# BuzzerBaseShieldv11.net
KiCad netlist of a schematic drawn in EAGLE
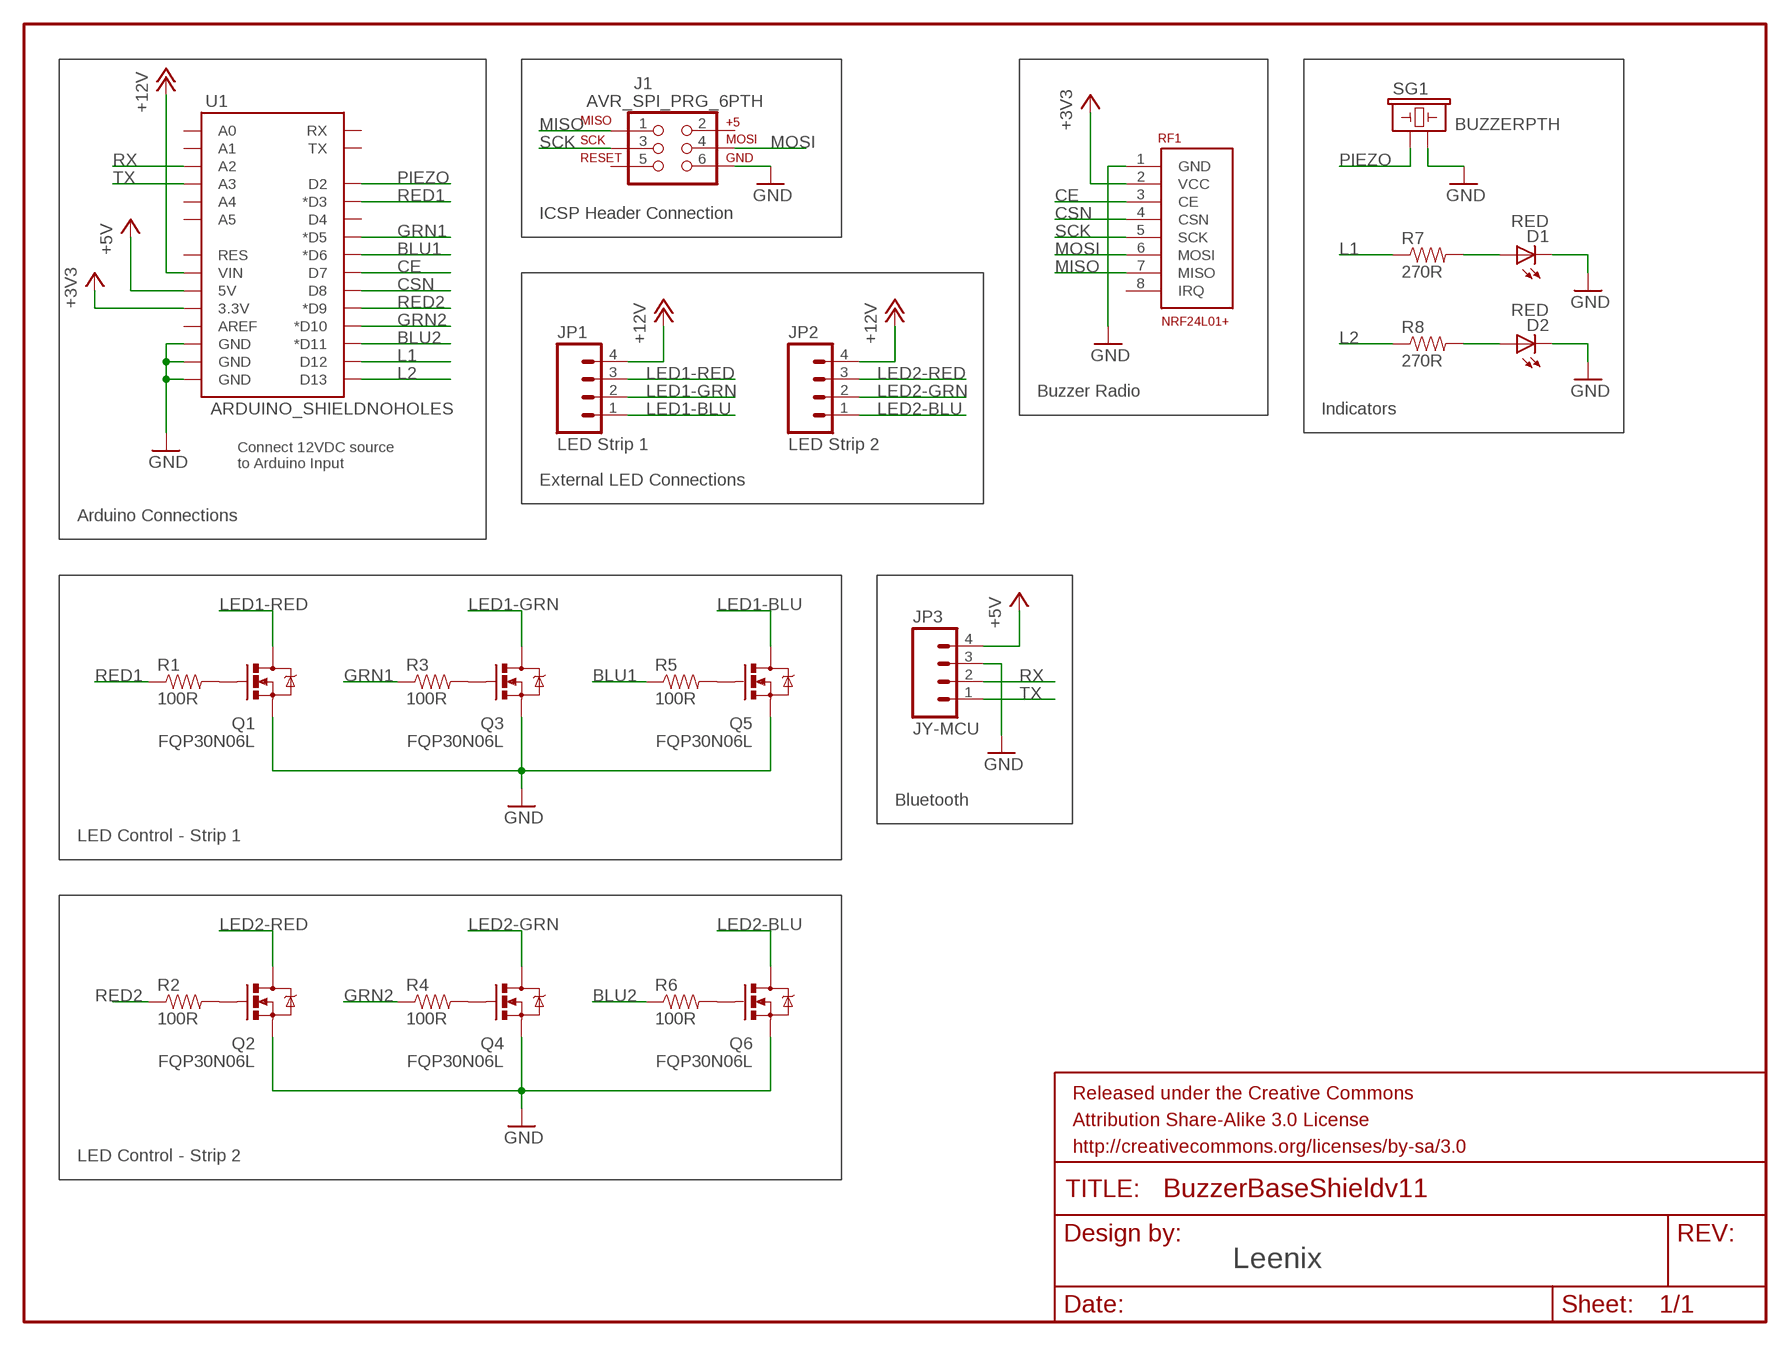
[diagram p0: schematic, sheet 1, part 1 of 2]
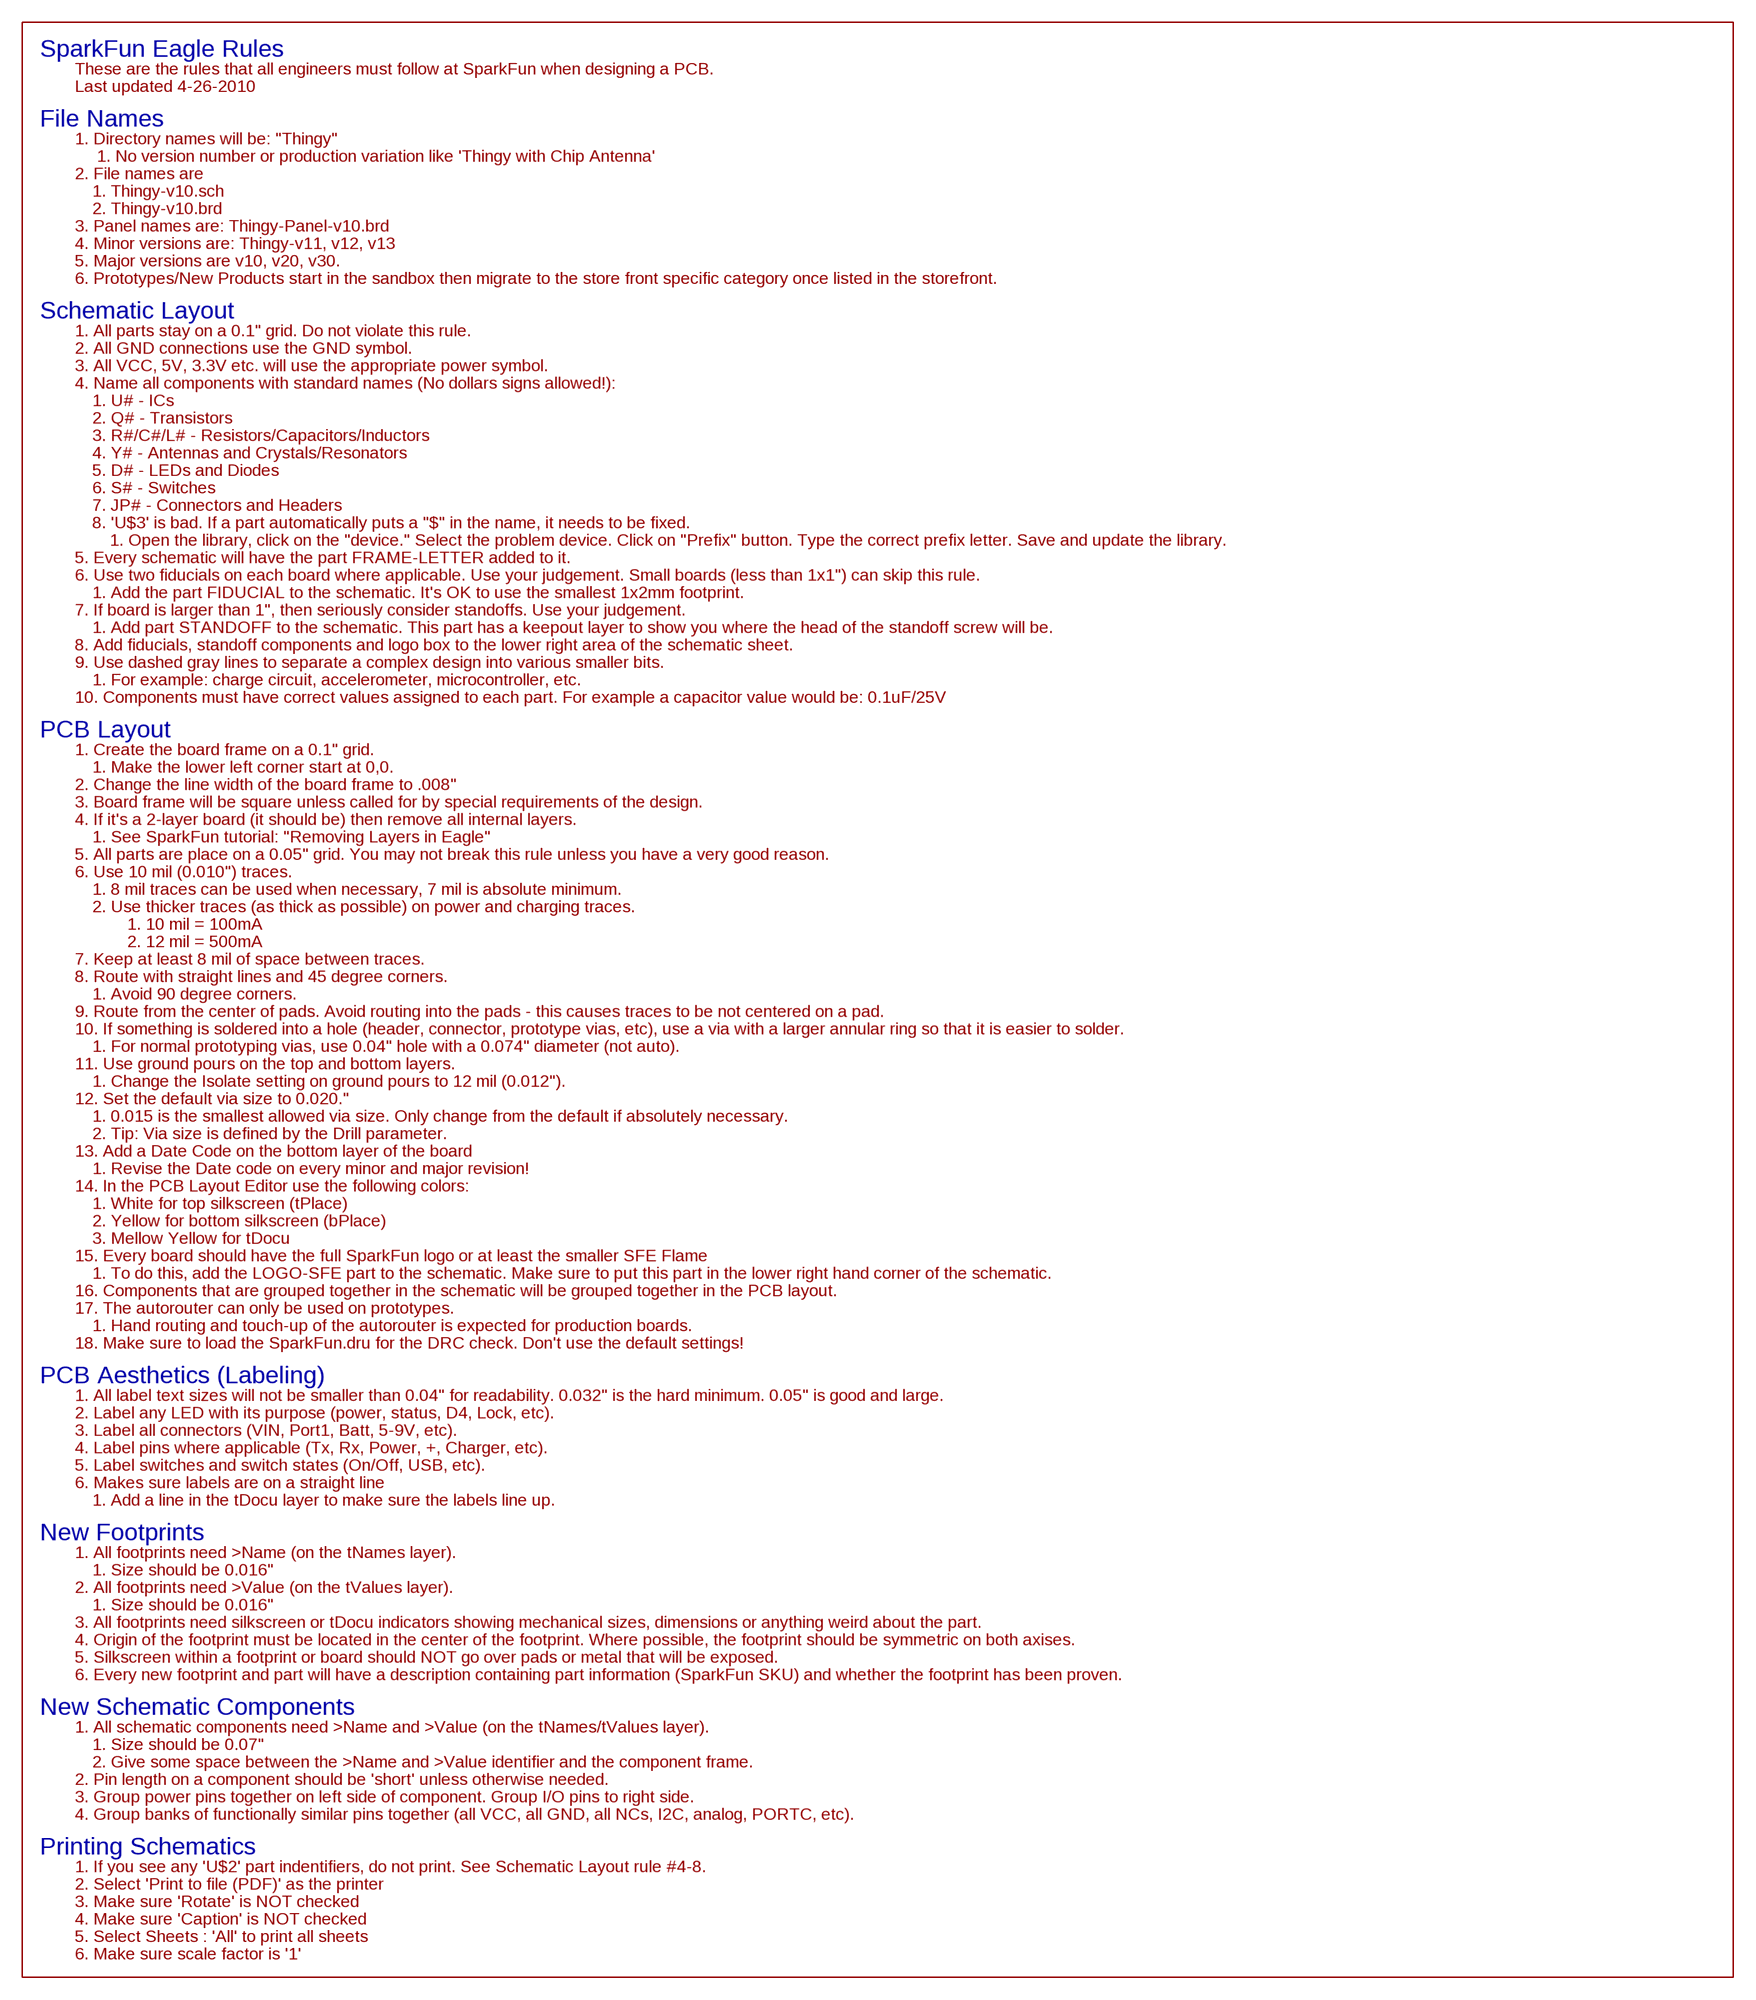
[diagram p1: schematic, sheet 1, part 2 of 2]

(export (version "E")
  (design (tool "Eeschema 10.0.6"))
  (components
    (comp (ref "D1")
      (value "RED")
      (footprint "eagle-import:LED-1206")
      (libsource (lib "eagle-import") (part "LED-RED1206"))
    )
    (comp (ref "D2")
      (value "RED")
      (footprint "eagle-import:LED-1206")
      (libsource (lib "eagle-import") (part "LED-RED1206"))
    )
    (comp (ref "FRAME1")
      (value "FRAME-LETTER")
      (footprint "eagle-import:CREATIVE_COMMONS")
      (libsource (lib "eagle-import") (part "FRAME-LETTER"))
    )
    (comp (ref "J1")
      (value "AVR_SPI_PRG_6PTH")
      (footprint "eagle-import:2X3")
      (libsource (lib "eagle-import") (part "AVR_SPI_PRG_6PTH"))
    )
    (comp (ref "JP1")
      (value "LED Strip 1")
      (footprint "eagle-import:1X04_LONGPADS")
      (libsource (lib "eagle-import") (part "M04LONGPADS"))
    )
    (comp (ref "JP2")
      (value "LED Strip 2")
      (footprint "eagle-import:1X04_LONGPADS")
      (libsource (lib "eagle-import") (part "M04LONGPADS"))
    )
    (comp (ref "JP3")
      (value "JY-MCU")
      (footprint "eagle-import:1X04")
      (libsource (lib "eagle-import") (part "M04PTH"))
    )
    (comp (ref "Q1")
      (value "FQP30N06L")
      (footprint "eagle-import:TO220V")
      (libsource (lib "eagle-import") (part "MOSFET-NCHANNELFQP30N06L"))
    )
    (comp (ref "Q2")
      (value "FQP30N06L")
      (footprint "eagle-import:TO220V")
      (libsource (lib "eagle-import") (part "MOSFET-NCHANNELFQP30N06L"))
    )
    (comp (ref "Q3")
      (value "FQP30N06L")
      (footprint "eagle-import:TO220V")
      (libsource (lib "eagle-import") (part "MOSFET-NCHANNELFQP30N06L"))
    )
    (comp (ref "Q4")
      (value "FQP30N06L")
      (footprint "eagle-import:TO220V")
      (libsource (lib "eagle-import") (part "MOSFET-NCHANNELFQP30N06L"))
    )
    (comp (ref "Q5")
      (value "FQP30N06L")
      (footprint "eagle-import:TO220V")
      (libsource (lib "eagle-import") (part "MOSFET-NCHANNELFQP30N06L"))
    )
    (comp (ref "Q6")
      (value "FQP30N06L")
      (footprint "eagle-import:TO220V")
      (libsource (lib "eagle-import") (part "MOSFET-NCHANNELFQP30N06L"))
    )
    (comp (ref "R1")
      (value "100R")
      (footprint "eagle-import:1206")
      (libsource (lib "eagle-import") (part "RESISTOR1206"))
    )
    (comp (ref "R2")
      (value "100R")
      (footprint "eagle-import:1206")
      (libsource (lib "eagle-import") (part "RESISTOR1206"))
    )
    (comp (ref "R3")
      (value "100R")
      (footprint "eagle-import:1206")
      (libsource (lib "eagle-import") (part "RESISTOR1206"))
    )
    (comp (ref "R4")
      (value "100R")
      (footprint "eagle-import:1206")
      (libsource (lib "eagle-import") (part "RESISTOR1206"))
    )
    (comp (ref "R5")
      (value "100R")
      (footprint "eagle-import:1206")
      (libsource (lib "eagle-import") (part "RESISTOR1206"))
    )
    (comp (ref "R6")
      (value "100R")
      (footprint "eagle-import:1206")
      (libsource (lib "eagle-import") (part "RESISTOR1206"))
    )
    (comp (ref "R7")
      (value "270R")
      (footprint "eagle-import:1206")
      (libsource (lib "eagle-import") (part "RESISTOR1206"))
    )
    (comp (ref "R8")
      (value "270R")
      (footprint "eagle-import:1206")
      (libsource (lib "eagle-import") (part "RESISTOR1206"))
    )
    (comp (ref "RF1")
      (value "NRF24L01+")
      (footprint "eagle-import:NRF24L01+-HEADER")
      (libsource (lib "eagle-import") (part "NRF24L01+"))
    )
    (comp (ref "SG1")
      (value "BUZZERPTH")
      (footprint "eagle-import:BUZZER-12MM")
      (libsource (lib "eagle-import") (part "BUZZERPTH"))
    )
    (comp (ref "U1")
      (value "ARDUINO_SHIELDNOHOLES")
      (footprint "eagle-import:DUEMILANOVE_SHIELD_NOHOLES")
      (libsource (lib "eagle-import") (part "ARDUINO_SHIELDNOHOLES"))
    )
  )
  (nets
    (net (code "1") (name "+3V3") (class "Default")
      (node (ref "RF1") (pin "2") (pinfunction "VCC_2") (pintype "power_in"))
      (node (ref "U1") (pin "3.3V") (pinfunction "3.3V_3.3V") (pintype "bidirectional"))
    )
    (net (code "2") (name "+5V") (class "Default")
      (node (ref "JP3") (pin "4") (pinfunction "4_4") (pintype "passive"))
      (node (ref "U1") (pin "5V") (pinfunction "5V_5V") (pintype "bidirectional"))
    )
    (net (code "3") (name "+12V") (class "Default")
      (node (ref "JP1") (pin "4") (pinfunction "4_4") (pintype "passive"))
      (node (ref "JP2") (pin "4") (pinfunction "4_4") (pintype "passive"))
      (node (ref "U1") (pin "VIN") (pinfunction "VIN_VIN") (pintype "bidirectional"))
    )
    (net (code "4") (name "/BLU1") (class "Default")
      (node (ref "R5") (pin "1") (pinfunction "1_1") (pintype "passive"))
      (node (ref "U1") (pin "D6") (pinfunction "*D6_D6") (pintype "bidirectional"))
    )
    (net (code "5") (name "/BLU2") (class "Default")
      (node (ref "R6") (pin "1") (pinfunction "1_1") (pintype "passive"))
      (node (ref "U1") (pin "D11") (pinfunction "*D11_D11") (pintype "bidirectional"))
    )
    (net (code "6") (name "/CE") (class "Default")
      (node (ref "RF1") (pin "3") (pinfunction "CE_3") (pintype "bidirectional"))
      (node (ref "U1") (pin "D7") (pinfunction "D7_D7") (pintype "bidirectional"))
    )
    (net (code "7") (name "/CSN") (class "Default")
      (node (ref "RF1") (pin "4") (pinfunction "CSN_4") (pintype "bidirectional"))
      (node (ref "U1") (pin "D8") (pinfunction "D8_D8") (pintype "bidirectional"))
    )
    (net (code "8") (name "/GRN1") (class "Default")
      (node (ref "R3") (pin "1") (pinfunction "1_1") (pintype "passive"))
      (node (ref "U1") (pin "D5") (pinfunction "*D5_D5") (pintype "bidirectional"))
    )
    (net (code "9") (name "/GRN2") (class "Default")
      (node (ref "R4") (pin "1") (pinfunction "1_1") (pintype "passive"))
      (node (ref "U1") (pin "D10") (pinfunction "*D10_D10") (pintype "bidirectional"))
    )
    (net (code "10") (name "/L1") (class "Default")
      (node (ref "R7") (pin "1") (pinfunction "1_1") (pintype "passive"))
      (node (ref "U1") (pin "D12") (pinfunction "D12_D12") (pintype "bidirectional"))
    )
    (net (code "11") (name "/L2") (class "Default")
      (node (ref "R8") (pin "1") (pinfunction "1_1") (pintype "passive"))
      (node (ref "U1") (pin "D13") (pinfunction "D13_D13") (pintype "bidirectional"))
    )
    (net (code "12") (name "/LED1-BLU") (class "Default")
      (node (ref "JP1") (pin "1") (pinfunction "1_1") (pintype "passive"))
      (node (ref "Q5") (pin "2") (pinfunction "D_2") (pintype "passive"))
    )
    (net (code "13") (name "/LED1-GRN") (class "Default")
      (node (ref "JP1") (pin "2") (pinfunction "2_2") (pintype "passive"))
      (node (ref "Q3") (pin "2") (pinfunction "D_2") (pintype "passive"))
    )
    (net (code "14") (name "/LED1-RED") (class "Default")
      (node (ref "JP1") (pin "3") (pinfunction "3_3") (pintype "passive"))
      (node (ref "Q1") (pin "2") (pinfunction "D_2") (pintype "passive"))
    )
    (net (code "15") (name "/LED2-BLU") (class "Default")
      (node (ref "JP2") (pin "1") (pinfunction "1_1") (pintype "passive"))
      (node (ref "Q6") (pin "2") (pinfunction "D_2") (pintype "passive"))
    )
    (net (code "16") (name "/LED2-GRN") (class "Default")
      (node (ref "JP2") (pin "2") (pinfunction "2_2") (pintype "passive"))
      (node (ref "Q4") (pin "2") (pinfunction "D_2") (pintype "passive"))
    )
    (net (code "17") (name "/LED2-RED") (class "Default")
      (node (ref "JP2") (pin "3") (pinfunction "3_3") (pintype "passive"))
      (node (ref "Q2") (pin "2") (pinfunction "D_2") (pintype "passive"))
    )
    (net (code "18") (name "/MISO") (class "Default")
      (node (ref "J1") (pin "1") (pinfunction "1_1") (pintype "passive"))
      (node (ref "RF1") (pin "7") (pinfunction "MISO_7") (pintype "bidirectional"))
    )
    (net (code "19") (name "/MOSI") (class "Default")
      (node (ref "J1") (pin "4") (pinfunction "4_4") (pintype "passive"))
      (node (ref "RF1") (pin "6") (pinfunction "MOSI_6") (pintype "bidirectional"))
    )
    (net (code "20") (name "/PIEZO") (class "Default")
      (node (ref "SG1") (pin "+") (pinfunction "1_+") (pintype "passive"))
      (node (ref "U1") (pin "D2") (pinfunction "D2_D2") (pintype "bidirectional"))
    )
    (net (code "21") (name "/RED1") (class "Default")
      (node (ref "R1") (pin "1") (pinfunction "1_1") (pintype "passive"))
      (node (ref "U1") (pin "D3") (pinfunction "*D3_D3") (pintype "bidirectional"))
    )
    (net (code "22") (name "/RED2") (class "Default")
      (node (ref "R2") (pin "1") (pinfunction "1_1") (pintype "passive"))
      (node (ref "U1") (pin "D9") (pinfunction "*D9_D9") (pintype "bidirectional"))
    )
    (net (code "23") (name "/RX") (class "Default")
      (node (ref "JP3") (pin "2") (pinfunction "2_2") (pintype "passive"))
      (node (ref "U1") (pin "A2") (pinfunction "A2_A2") (pintype "bidirectional"))
    )
    (net (code "24") (name "/SCK") (class "Default")
      (node (ref "J1") (pin "3") (pinfunction "3_3") (pintype "passive"))
      (node (ref "RF1") (pin "5") (pinfunction "SCK_5") (pintype "bidirectional"))
    )
    (net (code "25") (name "/TX") (class "Default")
      (node (ref "JP3") (pin "1") (pinfunction "1_1") (pintype "passive"))
      (node (ref "U1") (pin "A3") (pinfunction "A3_A3") (pintype "bidirectional"))
    )
    (net (code "26") (name "GND") (class "Default")
      (node (ref "D1") (pin "C") (pinfunction "C_C") (pintype "passive"))
      (node (ref "D2") (pin "C") (pinfunction "C_C") (pintype "passive"))
      (node (ref "J1") (pin "6") (pinfunction "6_6") (pintype "passive"))
      (node (ref "JP3") (pin "3") (pinfunction "3_3") (pintype "passive"))
      (node (ref "Q1") (pin "3") (pinfunction "S_3") (pintype "passive"))
      (node (ref "Q2") (pin "3") (pinfunction "S_3") (pintype "passive"))
      (node (ref "Q3") (pin "3") (pinfunction "S_3") (pintype "passive"))
      (node (ref "Q4") (pin "3") (pinfunction "S_3") (pintype "passive"))
      (node (ref "Q5") (pin "3") (pinfunction "S_3") (pintype "passive"))
      (node (ref "Q6") (pin "3") (pinfunction "S_3") (pintype "passive"))
      (node (ref "RF1") (pin "1") (pinfunction "GND_1") (pintype "power_in"))
      (node (ref "SG1") (pin "-") (pinfunction "2_-") (pintype "passive"))
      (node (ref "U1") (pin "GND@0") (pinfunction "GND_GND@0") (pintype "bidirectional"))
      (node (ref "U1") (pin "GND@1") (pinfunction "GND_GND@1") (pintype "bidirectional"))
      (node (ref "U1") (pin "GND@2") (pinfunction "GND_GND@2") (pintype "bidirectional"))
    )
    (net (code "27") (name "Net-(D1-PadA)") (class "Default")
      (node (ref "D1") (pin "A") (pinfunction "A_A") (pintype "passive"))
      (node (ref "R7") (pin "2") (pinfunction "2_2") (pintype "passive"))
    )
    (net (code "28") (name "Net-(D2-PadA)") (class "Default")
      (node (ref "D2") (pin "A") (pinfunction "A_A") (pintype "passive"))
      (node (ref "R8") (pin "2") (pinfunction "2_2") (pintype "passive"))
    )
    (net (code "29") (name "Net-(Q1-G)") (class "Default")
      (node (ref "Q1") (pin "1") (pinfunction "G_1") (pintype "passive"))
      (node (ref "R1") (pin "2") (pinfunction "2_2") (pintype "passive"))
    )
    (net (code "30") (name "Net-(Q2-G)") (class "Default")
      (node (ref "Q2") (pin "1") (pinfunction "G_1") (pintype "passive"))
      (node (ref "R2") (pin "2") (pinfunction "2_2") (pintype "passive"))
    )
    (net (code "31") (name "Net-(Q3-G)") (class "Default")
      (node (ref "Q3") (pin "1") (pinfunction "G_1") (pintype "passive"))
      (node (ref "R3") (pin "2") (pinfunction "2_2") (pintype "passive"))
    )
    (net (code "32") (name "Net-(Q4-G)") (class "Default")
      (node (ref "Q4") (pin "1") (pinfunction "G_1") (pintype "passive"))
      (node (ref "R4") (pin "2") (pinfunction "2_2") (pintype "passive"))
    )
    (net (code "33") (name "Net-(Q5-G)") (class "Default")
      (node (ref "Q5") (pin "1") (pinfunction "G_1") (pintype "passive"))
      (node (ref "R5") (pin "2") (pinfunction "2_2") (pintype "passive"))
    )
    (net (code "34") (name "Net-(Q6-G)") (class "Default")
      (node (ref "Q6") (pin "1") (pinfunction "G_1") (pintype "passive"))
      (node (ref "R6") (pin "2") (pinfunction "2_2") (pintype "passive"))
    )
    (net (code "35") (name "unconnected-(J1-Pad2)") (class "Default")
      (node (ref "J1") (pin "2") (pinfunction "2_2") (pintype "passive"))
    )
    (net (code "36") (name "unconnected-(J1-Pad5)") (class "Default")
      (node (ref "J1") (pin "5") (pinfunction "5_5") (pintype "passive"))
    )
    (net (code "37") (name "unconnected-(RF1-IRQ-Pad8)") (class "Default")
      (node (ref "RF1") (pin "8") (pinfunction "IRQ_8") (pintype "bidirectional"))
    )
    (net (code "38") (name "unconnected-(U1-PadA0)") (class "Default")
      (node (ref "U1") (pin "A0") (pinfunction "A0_A0") (pintype "bidirectional"))
    )
    (net (code "39") (name "unconnected-(U1-PadA1)") (class "Default")
      (node (ref "U1") (pin "A1") (pinfunction "A1_A1") (pintype "bidirectional"))
    )
    (net (code "40") (name "unconnected-(U1-PadA4)") (class "Default")
      (node (ref "U1") (pin "A4") (pinfunction "A4_A4") (pintype "bidirectional"))
    )
    (net (code "41") (name "unconnected-(U1-PadA5)") (class "Default")
      (node (ref "U1") (pin "A5") (pinfunction "A5_A5") (pintype "bidirectional"))
    )
    (net (code "42") (name "unconnected-(U1-PadAREF)") (class "Default")
      (node (ref "U1") (pin "AREF") (pinfunction "AREF_AREF") (pintype "bidirectional"))
    )
    (net (code "43") (name "unconnected-(U1-PadD4)") (class "Default")
      (node (ref "U1") (pin "D4") (pinfunction "D4_D4") (pintype "bidirectional"))
    )
    (net (code "44") (name "unconnected-(U1-PadRES)") (class "Default")
      (node (ref "U1") (pin "RES") (pinfunction "RES_RES") (pintype "bidirectional"))
    )
    (net (code "45") (name "unconnected-(U1-PadRX)") (class "Default")
      (node (ref "U1") (pin "RX") (pinfunction "RX_RX") (pintype "bidirectional"))
    )
    (net (code "46") (name "unconnected-(U1-PadTX)") (class "Default")
      (node (ref "U1") (pin "TX") (pinfunction "TX_TX") (pintype "bidirectional"))
    )
  )
)
